# Usb.net
KiCad netlist of a schematic drawn in Altium Designer
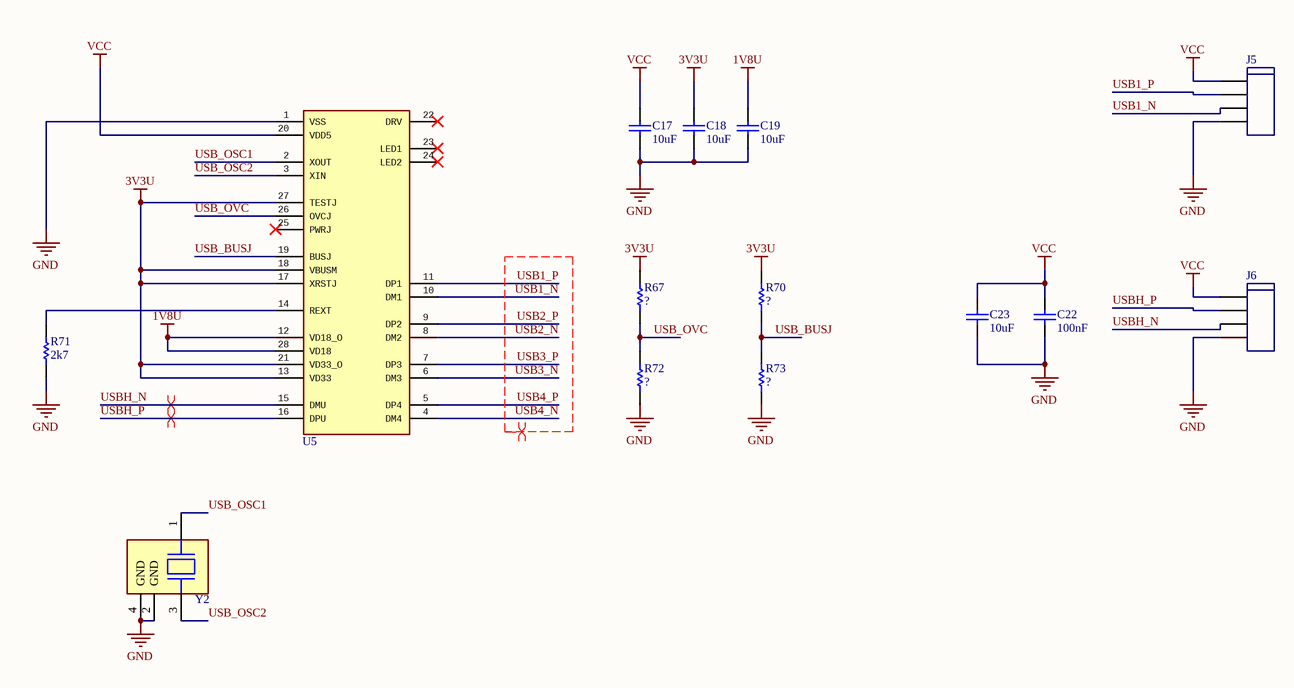
[diagram p0: Usb.SchDoc]

(export (version "E")
  (design (tool "Eeschema 10.0.6"))
  (components
    (comp (ref "C17")
      (value "10uF")
      (footprint "0603")
      (libsource (lib "LibDevs") (part "CAP 10uF 20% 0603"))
    )
    (comp (ref "C18")
      (value "10uF")
      (footprint "0603")
      (libsource (lib "LibDevs") (part "CAP 10uF 20% 0603"))
    )
    (comp (ref "C19")
      (value "10uF")
      (footprint "0603")
      (libsource (lib "LibDevs") (part "CAP 10uF 20% 0603"))
    )
    (comp (ref "C22")
      (value "100nF")
      (footprint "0603")
      (libsource (lib "LibDevs") (part "CAP 100nF 10V 10% 0603"))
    )
    (comp (ref "C23")
      (value "10uF")
      (footprint "0603")
      (libsource (lib "LibDevs") (part "CAP 10uF 20% 0603"))
    )
    (comp (ref "J5")
      (value "JST 4 PIN 1.25mm SMD_1")
      (footprint "JST 4 Pin 1.25mm")
      (libsource (lib "LibDevs") (part "JST 4 PIN 1.25mm SMD_1"))
    )
    (comp (ref "J6")
      (value "JST 4 PIN 1.25mm SMD_1")
      (footprint "JST 4 Pin 1.25mm")
      (libsource (lib "LibDevs") (part "JST 4 PIN 1.25mm SMD_1"))
    )
    (comp (ref "R67")
      (value "?")
      (footprint "0603")
      (fields (field (name "Comment") "RESISTOR GENERIC"))
      (libsource (lib "LibDevs") (part "RESISTOR GENERIC"))
    )
    (comp (ref "R70")
      (value "?")
      (footprint "0603")
      (fields (field (name "Comment") "RESISTOR GENERIC"))
      (libsource (lib "LibDevs") (part "RESISTOR GENERIC"))
    )
    (comp (ref "R71")
      (value "2k7")
      (footprint "0603")
      (fields (field (name "Comment") "RESISTOR GENERIC"))
      (libsource (lib "LibDevs") (part "RESISTOR GENERIC"))
    )
    (comp (ref "R72")
      (value "?")
      (footprint "0603")
      (fields (field (name "Comment") "RESISTOR GENERIC"))
      (libsource (lib "LibDevs") (part "RESISTOR GENERIC"))
    )
    (comp (ref "R73")
      (value "?")
      (footprint "0603")
      (fields (field (name "Comment") "RESISTOR GENERIC"))
      (libsource (lib "LibDevs") (part "RESISTOR GENERIC"))
    )
    (comp (ref "U5")
      (value "FE1.1S USB 2.0 hub IC")
      (footprint "FE1.1S_SSOP-28")
      (libsource (lib "LibDevs") (part "FE1.1S"))
    )
    (comp (ref "Y2")
      (value "XTAL S3212000121080 12MHz 30PPM")
      (footprint "LibDevs:SMD3225-4P")
      (description "Crystals 12MHz 10pF 30PPM -40 +85C")
      (fields (field (name "MANUFACTURER") "JGHC") (field (name "LCSC PART") "C479193"))
      (libsource (lib "LibDevs") (part "XTAL S3212000121080 12MHz 30PPM"))
    )
  )
  (nets
    (net (code "1") (name "/USB1_N") (class "Default")
      (node (ref "J5") (pin "3") (pinfunction "3_3") (pintype "passive"))
      (node (ref "U5") (pin "10") (pinfunction "DM1_10") (pintype "passive"))
    )
    (net (code "2") (name "/USB1_P") (class "Default")
      (node (ref "J5") (pin "2") (pinfunction "2_2") (pintype "passive"))
      (node (ref "U5") (pin "11") (pinfunction "DP1_11") (pintype "passive"))
    )
    (net (code "3") (name "/USB2_N") (class "Default")
      (node (ref "U5") (pin "8") (pinfunction "DM2_8") (pintype "passive"))
    )
    (net (code "4") (name "/USB2_P") (class "Default")
      (node (ref "U5") (pin "9") (pinfunction "DP2_9") (pintype "passive"))
    )
    (net (code "5") (name "/USB3_N") (class "Default")
      (node (ref "U5") (pin "6") (pinfunction "DM3_6") (pintype "passive"))
    )
    (net (code "6") (name "/USB3_P") (class "Default")
      (node (ref "U5") (pin "7") (pinfunction "DP3_7") (pintype "passive"))
    )
    (net (code "7") (name "/USB4_N") (class "Default")
      (node (ref "U5") (pin "4") (pinfunction "DM4_4") (pintype "passive"))
    )
    (net (code "8") (name "/USB4_P") (class "Default")
      (node (ref "U5") (pin "5") (pinfunction "DP4_5") (pintype "passive"))
    )
    (net (code "9") (name "/USBH_N") (class "Default")
      (node (ref "J6") (pin "3") (pinfunction "3_3") (pintype "passive"))
      (node (ref "U5") (pin "15") (pinfunction "DMU_15") (pintype "passive"))
    )
    (net (code "10") (name "/USBH_P") (class "Default")
      (node (ref "J6") (pin "2") (pinfunction "2_2") (pintype "passive"))
      (node (ref "U5") (pin "16") (pinfunction "DPU_16") (pintype "passive"))
    )
    (net (code "11") (name "/USB_BUSJ") (class "Default")
      (node (ref "R70") (pin "1") (pinfunction "1_1") (pintype "passive"))
      (node (ref "R73") (pin "2") (pinfunction "2_2") (pintype "passive"))
      (node (ref "U5") (pin "19") (pinfunction "BUSJ_19") (pintype "passive"))
    )
    (net (code "12") (name "/USB_OSC1") (class "Default")
      (node (ref "U5") (pin "2") (pinfunction "XOUT_2") (pintype "passive"))
      (node (ref "Y2") (pin "1") (pinfunction "1_1") (pintype "passive"))
    )
    (net (code "13") (name "/USB_OSC2") (class "Default")
      (node (ref "U5") (pin "3") (pinfunction "XIN_3") (pintype "passive"))
      (node (ref "Y2") (pin "3") (pinfunction "3_3") (pintype "passive"))
    )
    (net (code "14") (name "/USB_OVC") (class "Default")
      (node (ref "R67") (pin "1") (pinfunction "1_1") (pintype "passive"))
      (node (ref "R72") (pin "2") (pinfunction "2_2") (pintype "passive"))
      (node (ref "U5") (pin "26") (pinfunction "OVCJ_26") (pintype "passive"))
    )
    (net (code "15") (name "1V8U") (class "Default")
      (node (ref "C19") (pin "2") (pinfunction "2_2") (pintype "passive"))
      (node (ref "U5") (pin "12") (pinfunction "VD18_O_12") (pintype "passive"))
      (node (ref "U5") (pin "28") (pinfunction "VD18_28") (pintype "passive"))
    )
    (net (code "16") (name "3V3U") (class "Default")
      (node (ref "C18") (pin "2") (pinfunction "2_2") (pintype "passive"))
      (node (ref "R67") (pin "2") (pinfunction "2_2") (pintype "passive"))
      (node (ref "R70") (pin "2") (pinfunction "2_2") (pintype "passive"))
      (node (ref "U5") (pin "13") (pinfunction "VD33_13") (pintype "passive"))
      (node (ref "U5") (pin "17") (pinfunction "XRSTJ_17") (pintype "passive"))
      (node (ref "U5") (pin "18") (pinfunction "VBUSM_18") (pintype "passive"))
      (node (ref "U5") (pin "21") (pinfunction "VD33_O_21") (pintype "passive"))
      (node (ref "U5") (pin "27") (pinfunction "TESTJ_27") (pintype "passive"))
    )
    (net (code "17") (name "GND") (class "Default")
      (node (ref "C17") (pin "1") (pinfunction "1_1") (pintype "passive"))
      (node (ref "C18") (pin "1") (pinfunction "1_1") (pintype "passive"))
      (node (ref "C19") (pin "1") (pinfunction "1_1") (pintype "passive"))
      (node (ref "C22") (pin "1") (pinfunction "1_1") (pintype "passive"))
      (node (ref "C23") (pin "1") (pinfunction "1_1") (pintype "passive"))
      (node (ref "J5") (pin "4") (pinfunction "4_4") (pintype "passive"))
      (node (ref "J6") (pin "4") (pinfunction "4_4") (pintype "passive"))
      (node (ref "R71") (pin "1") (pinfunction "1_1") (pintype "passive"))
      (node (ref "R72") (pin "1") (pinfunction "1_1") (pintype "passive"))
      (node (ref "R73") (pin "1") (pinfunction "1_1") (pintype "passive"))
      (node (ref "U5") (pin "1") (pinfunction "VSS_1") (pintype "passive"))
      (node (ref "Y2") (pin "2") (pinfunction "GND_2") (pintype "power_in"))
      (node (ref "Y2") (pin "4") (pinfunction "GND_4") (pintype "power_in"))
    )
    (net (code "18") (name "Net-(U5-REXT)") (class "Default")
      (node (ref "R71") (pin "2") (pinfunction "2_2") (pintype "passive"))
      (node (ref "U5") (pin "14") (pinfunction "REXT_14") (pintype "passive"))
    )
    (net (code "19") (name "VCC") (class "Default")
      (node (ref "C17") (pin "2") (pinfunction "2_2") (pintype "passive"))
      (node (ref "C22") (pin "2") (pinfunction "2_2") (pintype "passive"))
      (node (ref "C23") (pin "2") (pinfunction "2_2") (pintype "passive"))
      (node (ref "J5") (pin "1") (pinfunction "1_1") (pintype "passive"))
      (node (ref "J6") (pin "1") (pinfunction "1_1") (pintype "passive"))
      (node (ref "U5") (pin "20") (pinfunction "VDD5_20") (pintype "passive"))
    )
    (net (code "20") (name "unconnected-(U5-DRV-Pad22)") (class "Default")
      (node (ref "U5") (pin "22") (pinfunction "DRV_22") (pintype "passive+no_connect"))
    )
    (net (code "21") (name "unconnected-(U5-LED1-Pad23)") (class "Default")
      (node (ref "U5") (pin "23") (pinfunction "LED1_23") (pintype "passive+no_connect"))
    )
    (net (code "22") (name "unconnected-(U5-LED2-Pad24)") (class "Default")
      (node (ref "U5") (pin "24") (pinfunction "LED2_24") (pintype "passive+no_connect"))
    )
    (net (code "23") (name "unconnected-(U5-PWRJ-Pad25)") (class "Default")
      (node (ref "U5") (pin "25") (pinfunction "PWRJ_25") (pintype "passive+no_connect"))
    )
  )
)
